# PC_Starter.net
KiCad netlist of a schematic drawn in Altium Designer
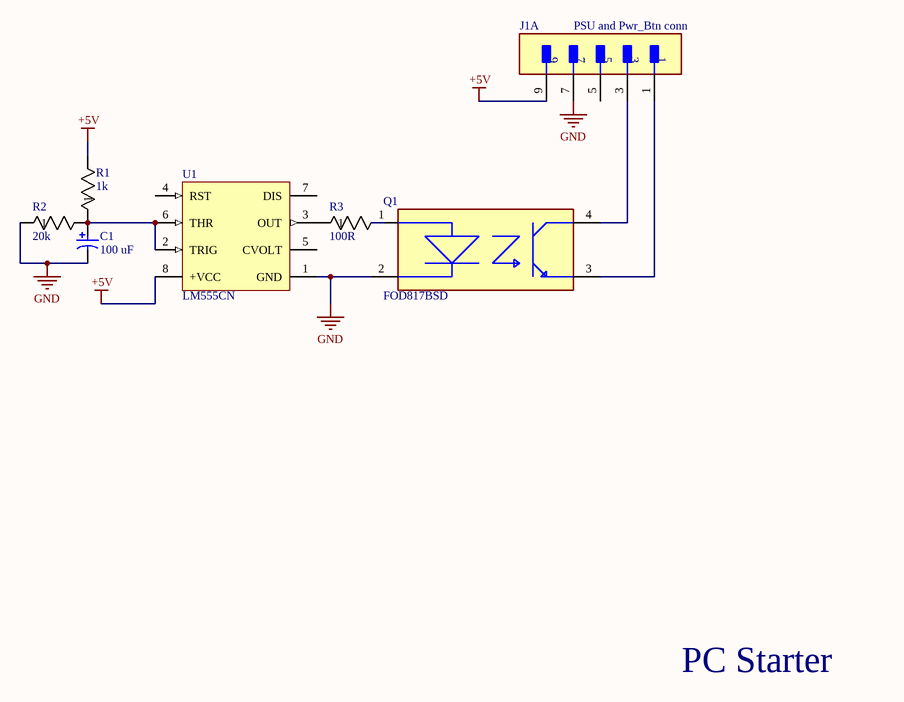
[diagram p0: PC_Starter.SchDoc]

(export (version "E")
  (design (tool "Eeschema 10.0.6"))
  (components
    (comp (ref "C1")
      (value "100 uF")
      (footprint "NIC-RNS-8x11.5-2_V")
      (description "Aluminum Electrolytic Capacitor, 100 uF +/-20%, 10 V, -55 to 105 degC, 2-Pin THD, RoHS")
      (fields (field (name "PARTNUMBER") "RNS1A101MDN1KX") (field (name "MANUFACTURER") "Nichicon"))
      (libsource (lib "Altium Content Vault") (part "NIC-CAP-P-2"))
    )
    (comp (ref "J1")
      (value "PSU and Pwr_Btn conn")
      (footprint "FP-M50-3600542-MFG")
      (description "CONN HEADER SMD 10POS 1.27MM")
      (libsource (lib "Altium Content Vault") (part "046167e5aeff191f0d596edc0695a2d"))
    )
    (comp (ref "Q1")
      (value "FOD817BSD")
      (footprint "FP-709AH-MFG")
      (description "OPTOISOLATOR 5KV TRANSISTOR 4SMD")
      (fields
        (field (name "MANUFACTURER") "ON Semiconductor")
        (field (name "OCTOPART") "https://octopart.com/fod817bsd-on+semiconductor-84327540")
      )
      (libsource (lib "Altium Content Vault") (part "dac7be9ee7c3f9c10b1b8b15490eb21"))
    )
    (comp (ref "R1")
      (value "1k")
      (footprint "RES_AC05_VIS")
      (description "AC05000001001JAC00 Resistor, Wirewound, Res 1 Kilohms, Pwr-Rtg 5 W, Tol 5%, Axial, Ceramic Core")
      (fields (field (name "TOLERANCE") "5%"))
      (libsource (lib "Altium Content Vault") (part "AC05000001001JAC00"))
    )
    (comp (ref "R2")
      (value "20k")
      (footprint "RES_AC05_VIS")
      (description "AC05000001001JAC00 Resistor, Wirewound, Res 1 Kilohms, Pwr-Rtg 5 W, Tol 5%, Axial, Ceramic Core")
      (fields (field (name "TOLERANCE") "5%"))
      (libsource (lib "Altium Content Vault") (part "AC05000001001JAC00"))
    )
    (comp (ref "R3")
      (value "100R")
      (footprint "RES_AC01_VIS")
      (description "VISHAY AC01000001000JA100 Through Hole Resistor, 100 ohm, Axial Leaded, 1 W, 5%, AC Series")
      (fields (field (name "TOLERANCE") "5%"))
      (libsource (lib "Altium Content Vault") (part "AC01000001000JA100"))
    )
    (comp (ref "U1")
      (value "LM555CN")
      (footprint "N08E")
      (description "Timer, 8-pin MDIP")
      (fields (field (name "MANUFACTURER") "National Semiconductor"))
      (libsource (lib "Altium Content Vault") (part "AN-TIMER-LM555-8"))
    )
  )
  (nets
    (net (code "1") (name "+5V") (class "Default")
      (node (ref "J1") (pin "9") (pinfunction "9_9") (pintype "passive"))
      (node (ref "R1") (pin "2") (pinfunction "2_2") (pintype "passive"))
      (node (ref "U1") (pin "8") (pinfunction "+VCC_8") (pintype "power_in"))
    )
    (net (code "2") (name "GND") (class "Default")
      (node (ref "C1") (pin "2") (pinfunction "2_2") (pintype "passive"))
      (node (ref "J1") (pin "7") (pinfunction "7_7") (pintype "passive"))
      (node (ref "Q1") (pin "2") (pinfunction "C_2") (pintype "passive"))
      (node (ref "R2") (pin "1") (pinfunction "1_1") (pintype "passive"))
      (node (ref "U1") (pin "1") (pinfunction "GND_1") (pintype "power_in"))
    )
    (net (code "3") (name "Net-(J1-Pad3)") (class "Default")
      (node (ref "J1") (pin "3") (pinfunction "3_3") (pintype "passive"))
      (node (ref "Q1") (pin "4") (pinfunction "C_4") (pintype "passive"))
    )
    (net (code "4") (name "Net-(Q1-A)") (class "Default")
      (node (ref "Q1") (pin "1") (pinfunction "A_1") (pintype "passive"))
      (node (ref "R3") (pin "2") (pinfunction "2_2") (pintype "passive"))
    )
    (net (code "5") (name "Net-(Q1-E)") (class "Default")
      (node (ref "J1") (pin "1") (pinfunction "1_1") (pintype "passive"))
      (node (ref "Q1") (pin "3") (pinfunction "E_3") (pintype "passive"))
    )
    (net (code "6") (name "Net-(U1-OUT)") (class "Default")
      (node (ref "R3") (pin "1") (pinfunction "1_1") (pintype "passive"))
      (node (ref "U1") (pin "3") (pinfunction "OUT_3") (pintype "output"))
    )
    (net (code "7") (name "Net-(U1-THR)") (class "Default")
      (node (ref "C1") (pin "1") (pinfunction "1_1") (pintype "passive"))
      (node (ref "R1") (pin "1") (pinfunction "1_1") (pintype "passive"))
      (node (ref "R2") (pin "2") (pinfunction "2_2") (pintype "passive"))
      (node (ref "U1") (pin "2") (pinfunction "TRIG_2") (pintype "input"))
      (node (ref "U1") (pin "6") (pinfunction "THR_6") (pintype "input"))
    )
    (net (code "8") (name "unconnected-(J1-Pad5)") (class "Default")
      (node (ref "J1") (pin "5") (pinfunction "5_5") (pintype "passive"))
    )
    (net (code "9") (name "unconnected-(U1-CVOLT-Pad5)") (class "Default")
      (node (ref "U1") (pin "5") (pinfunction "CVOLT_5") (pintype "passive"))
    )
    (net (code "10") (name "unconnected-(U1-DIS-Pad7)") (class "Default")
      (node (ref "U1") (pin "7") (pinfunction "DIS_7") (pintype "open_collector"))
    )
    (net (code "11") (name "unconnected-(U1-RST-Pad4)") (class "Default")
      (node (ref "U1") (pin "4") (pinfunction "RST_4") (pintype "input"))
    )
  )
)
